# SCH_ERangerBeads_2023-05-25.net
KiCad netlist of a schematic drawn in EasyEDA
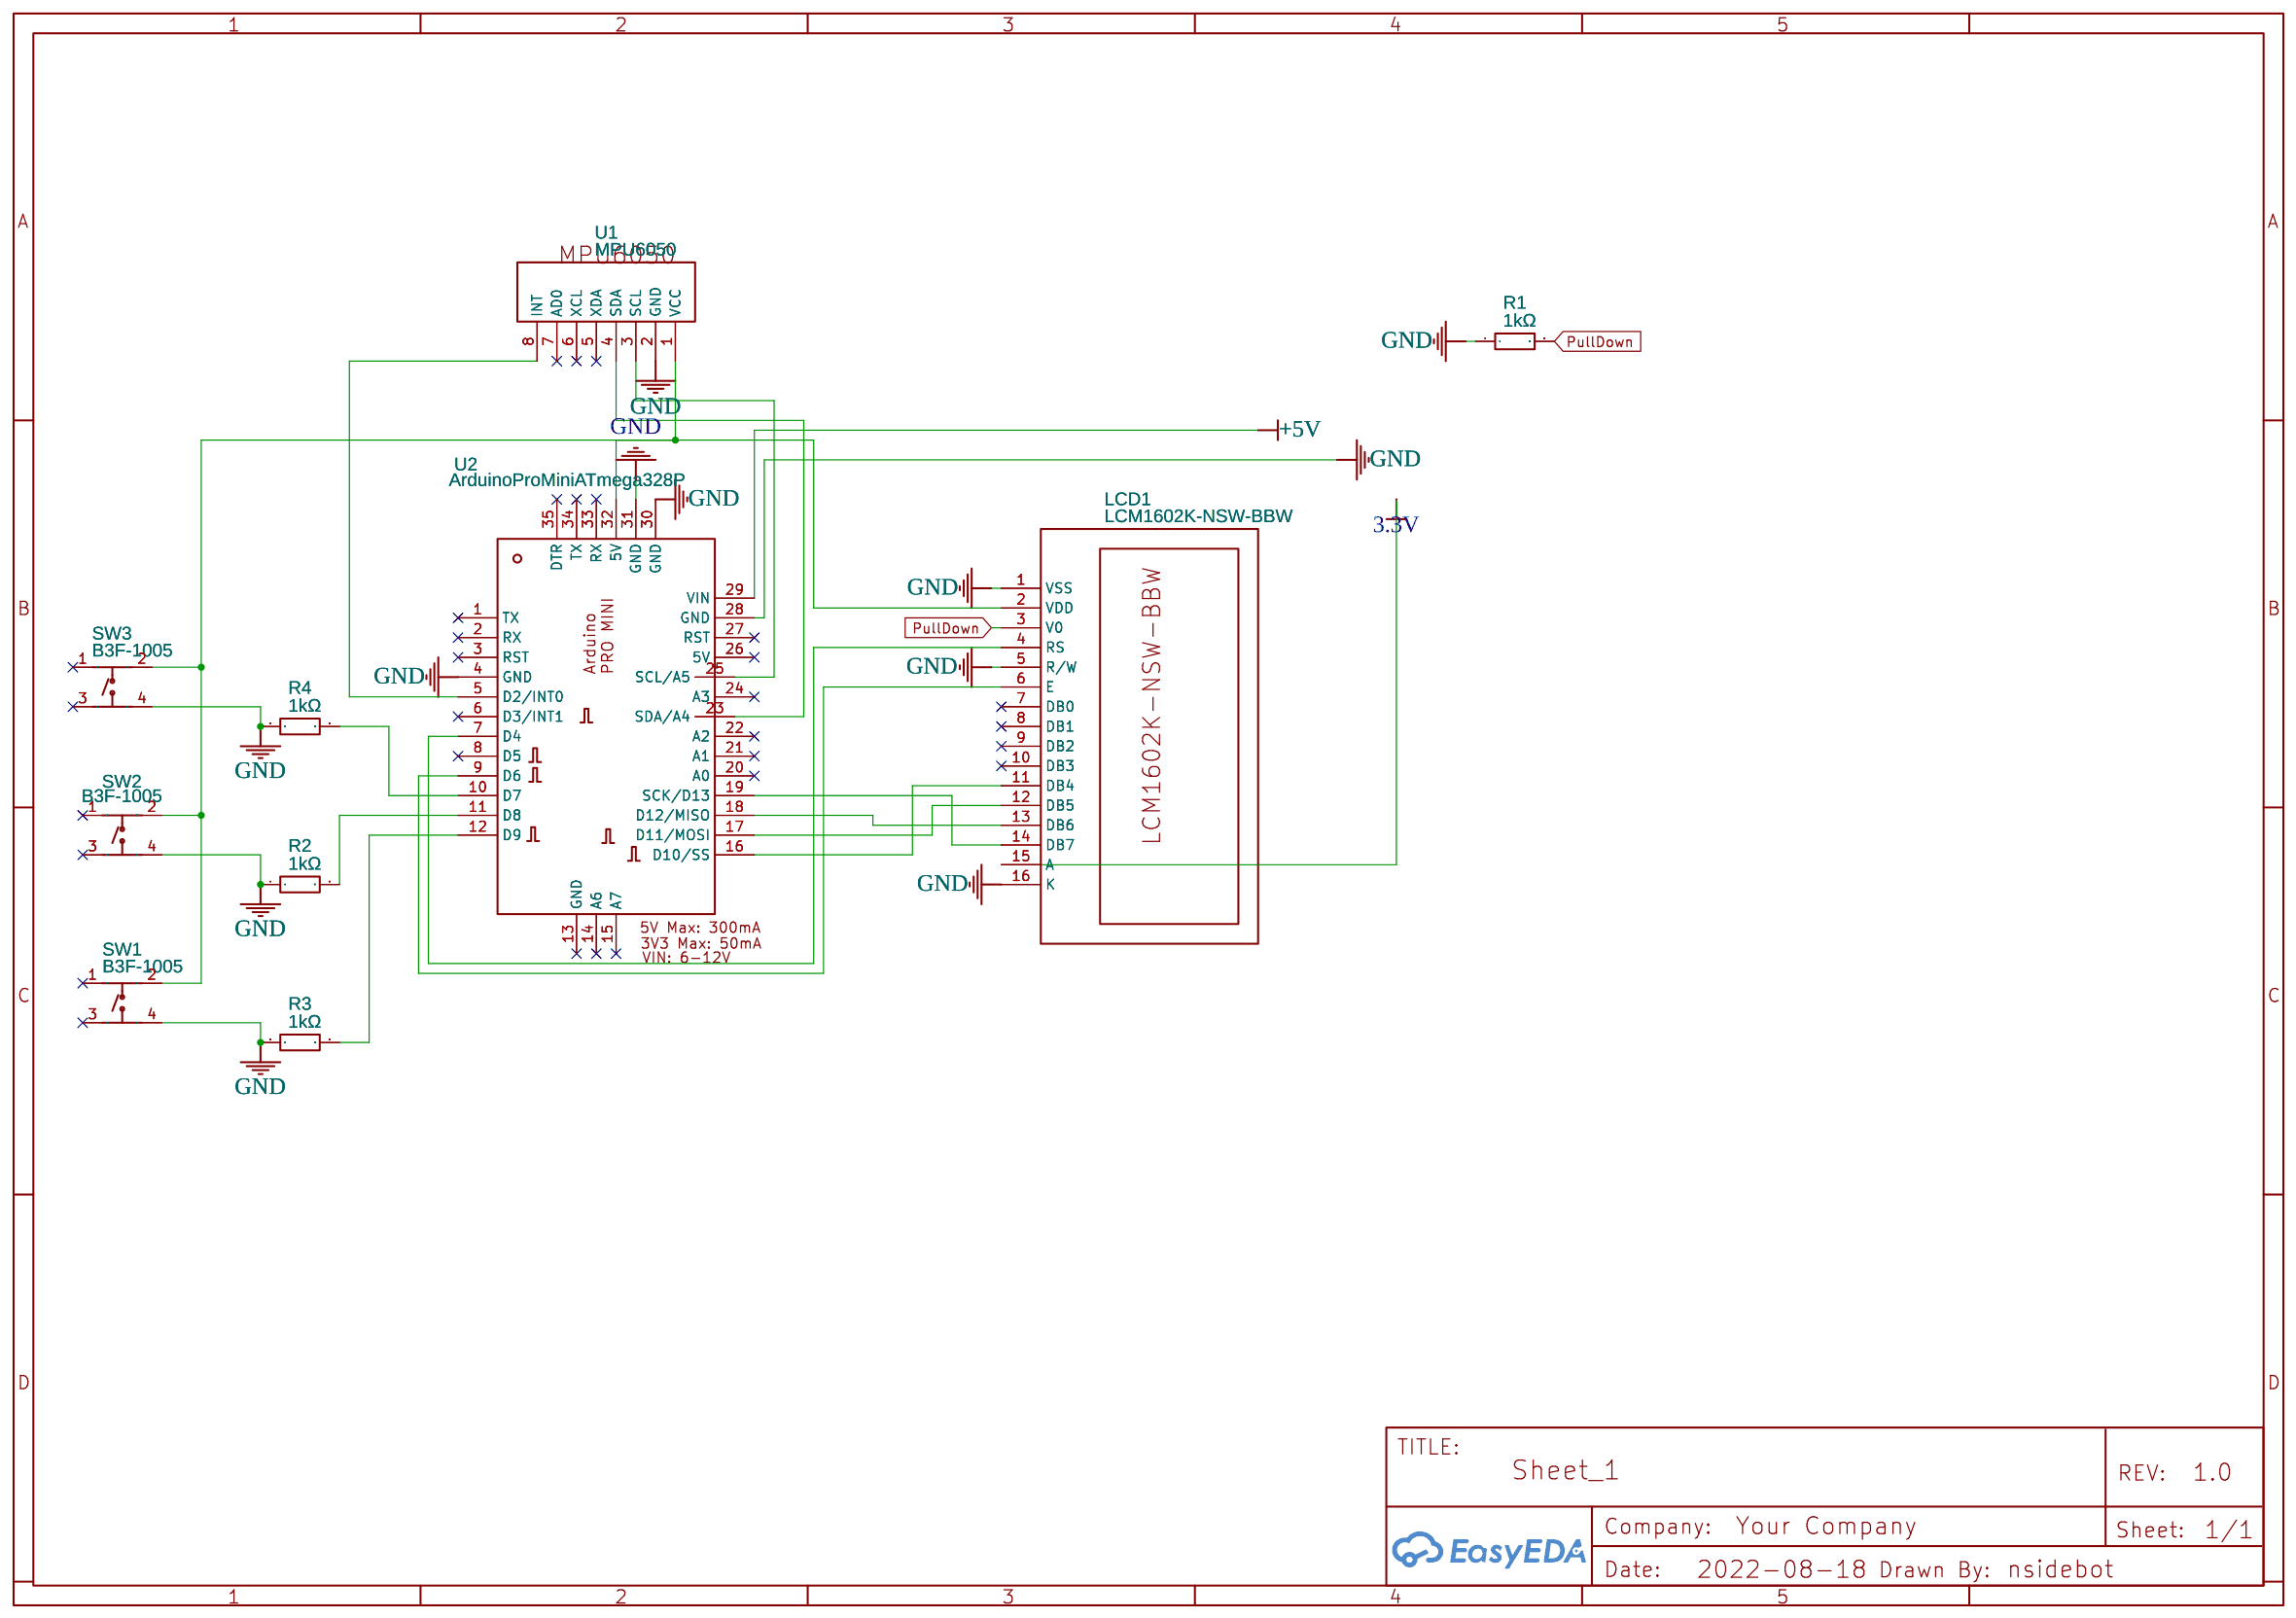
[diagram p0: schematic sheet]

(export (version "E")
  (design (tool "Eeschema 10.0.6"))
  (components
    (comp (ref "LCD1")
      (value "LCM1602K-NSW-BBW")
      (fields (field (name "BOM_Supplier Part") "C83275"))
      (libsource (lib "") (part "LCM1602K-NSW-BBW"))
    )
    (comp (ref "R1")
      (value "1kΩ")
      (fields
        (field (name "BOM_Manufacturer Part") "0603WAJ0102T5E")
        (field (name "BOM_Supplier Part") "C25585")
      )
      (libsource (lib "") (part "0603WAJ0102T5E"))
    )
    (comp (ref "R2")
      (value "1kΩ")
      (fields
        (field (name "BOM_Manufacturer Part") "0603WAJ0102T5E")
        (field (name "BOM_Supplier Part") "C25585")
      )
      (libsource (lib "") (part "0603WAJ0102T5E"))
    )
    (comp (ref "R3")
      (value "1kΩ")
      (fields
        (field (name "BOM_Manufacturer Part") "0603WAJ0102T5E")
        (field (name "BOM_Supplier Part") "C25585")
      )
      (libsource (lib "") (part "0603WAJ0102T5E"))
    )
    (comp (ref "R4")
      (value "1kΩ")
      (fields
        (field (name "BOM_Manufacturer Part") "0603WAJ0102T5E")
        (field (name "BOM_Supplier Part") "C25585")
      )
      (libsource (lib "") (part "0603WAJ0102T5E"))
    )
    (comp (ref "SW1")
      (value "B3F-1005")
      (fields (field (name "BOM_Supplier Part") "C397293"))
      (libsource (lib "") (part "B3F-1005"))
    )
    (comp (ref "SW2")
      (value "B3F-1005")
      (fields (field (name "BOM_Supplier Part") "C397293"))
      (libsource (lib "") (part "B3F-1005"))
    )
    (comp (ref "SW3")
      (value "B3F-1005")
      (fields (field (name "BOM_Supplier Part") "C397293"))
      (libsource (lib "") (part "B3F-1005"))
    )
    (comp (ref "U1") (value "MPU6050") (libsource (lib "") (part "MPU6050")))
    (comp (ref "U2")
      (value "ArduinoProMiniATmega328P")
      (libsource (lib "") (part "ArduinoProMiniATmega328P"))
    )
  )
  (nets
    (net (code "1") (name "+5V") (class "Default")
      (node (ref "U2") (pin "29") (pinfunction "VIN_29") (pintype "unspecified"))
    )
    (net (code "2") (name "3.3V") (class "Default")
      (node (ref "LCD1") (pin "15") (pinfunction "A_15") (pintype "unspecified"))
    )
    (net (code "3") (name "GND") (class "Default")
      (node (ref "LCD1") (pin "1") (pinfunction "VSS_1") (pintype "unspecified"))
      (node (ref "LCD1") (pin "16") (pinfunction "K_16") (pintype "unspecified"))
      (node (ref "LCD1") (pin "5") (pinfunction "R/W_5") (pintype "unspecified"))
      (node (ref "R1") (pin "1") (pinfunction "1_1") (pintype "input"))
      (node (ref "R2") (pin "1") (pinfunction "1_1") (pintype "input"))
      (node (ref "R3") (pin "1") (pinfunction "1_1") (pintype "input"))
      (node (ref "R4") (pin "1") (pinfunction "1_1") (pintype "input"))
      (node (ref "SW1") (pin "4") (pinfunction "4_4") (pintype "unspecified"))
      (node (ref "SW2") (pin "4") (pinfunction "4_4") (pintype "unspecified"))
      (node (ref "SW3") (pin "4") (pinfunction "4_4") (pintype "unspecified"))
      (node (ref "U1") (pin "2") (pinfunction "GND_2") (pintype "unspecified"))
      (node (ref "U2") (pin "28") (pinfunction "GND_28") (pintype "unspecified"))
      (node (ref "U2") (pin "30") (pinfunction "GND_30") (pintype "unspecified"))
      (node (ref "U2") (pin "31") (pinfunction "GND_31") (pintype "unspecified"))
      (node (ref "U2") (pin "4") (pinfunction "GND_4") (pintype "unspecified"))
    )
    (net (code "4") (name "Net-(LCD1-DB4)") (class "Default")
      (node (ref "LCD1") (pin "11") (pinfunction "DB4_11") (pintype "unspecified"))
      (node (ref "U2") (pin "16") (pinfunction "D10/SS_16") (pintype "unspecified"))
    )
    (net (code "5") (name "Net-(LCD1-DB5)") (class "Default")
      (node (ref "LCD1") (pin "12") (pinfunction "DB5_12") (pintype "unspecified"))
      (node (ref "U2") (pin "17") (pinfunction "D11/MOSI_17") (pintype "unspecified"))
    )
    (net (code "6") (name "Net-(LCD1-DB6)") (class "Default")
      (node (ref "LCD1") (pin "13") (pinfunction "DB6_13") (pintype "unspecified"))
      (node (ref "U2") (pin "18") (pinfunction "D12/MISO_18") (pintype "unspecified"))
    )
    (net (code "7") (name "Net-(LCD1-DB7)") (class "Default")
      (node (ref "LCD1") (pin "14") (pinfunction "DB7_14") (pintype "unspecified"))
      (node (ref "U2") (pin "19") (pinfunction "SCK/D13_19") (pintype "unspecified"))
    )
    (net (code "8") (name "Net-(LCD1-E)") (class "Default")
      (node (ref "LCD1") (pin "6") (pinfunction "E_6") (pintype "unspecified"))
      (node (ref "U2") (pin "9") (pinfunction "D6_9") (pintype "unspecified"))
    )
    (net (code "9") (name "Net-(LCD1-RS)") (class "Default")
      (node (ref "LCD1") (pin "4") (pinfunction "RS_4") (pintype "unspecified"))
      (node (ref "U2") (pin "7") (pinfunction "D4_7") (pintype "unspecified"))
    )
    (net (code "10") (name "Net-(LCD1-VDD)") (class "Default")
      (node (ref "LCD1") (pin "2") (pinfunction "VDD_2") (pintype "unspecified"))
      (node (ref "SW1") (pin "2") (pinfunction "2_2") (pintype "unspecified"))
      (node (ref "SW2") (pin "2") (pinfunction "2_2") (pintype "unspecified"))
      (node (ref "SW3") (pin "2") (pinfunction "2_2") (pintype "unspecified"))
      (node (ref "U1") (pin "1") (pinfunction "VCC_1") (pintype "unspecified"))
      (node (ref "U2") (pin "32") (pinfunction "5V_32") (pintype "unspecified"))
    )
    (net (code "11") (name "Net-(U1-INT)") (class "Default")
      (node (ref "U1") (pin "8") (pinfunction "INT_8") (pintype "unspecified"))
      (node (ref "U2") (pin "5") (pinfunction "D2/INT0_5") (pintype "unspecified"))
    )
    (net (code "12") (name "Net-(U1-SCL)") (class "Default")
      (node (ref "U1") (pin "3") (pinfunction "SCL_3") (pintype "unspecified"))
      (node (ref "U2") (pin "25") (pinfunction "SCL/A5_25") (pintype "unspecified"))
    )
    (net (code "13") (name "Net-(U1-SDA)") (class "Default")
      (node (ref "U1") (pin "4") (pinfunction "SDA_4") (pintype "unspecified"))
      (node (ref "U2") (pin "23") (pinfunction "SDA/A4_23") (pintype "unspecified"))
    )
    (net (code "14") (name "Net-(U2-D7)") (class "Default")
      (node (ref "R4") (pin "2") (pinfunction "2_2") (pintype "input"))
      (node (ref "U2") (pin "10") (pinfunction "D7_10") (pintype "unspecified"))
    )
    (net (code "15") (name "Net-(U2-D8)") (class "Default")
      (node (ref "R2") (pin "2") (pinfunction "2_2") (pintype "input"))
      (node (ref "U2") (pin "11") (pinfunction "D8_11") (pintype "unspecified"))
    )
    (net (code "16") (name "Net-(U2-D9)") (class "Default")
      (node (ref "R3") (pin "2") (pinfunction "2_2") (pintype "input"))
      (node (ref "U2") (pin "12") (pinfunction "D9_12") (pintype "unspecified"))
    )
    (net (code "17") (name "PullDown") (class "Default")
      (node (ref "LCD1") (pin "3") (pinfunction "V0_3") (pintype "unspecified"))
      (node (ref "R1") (pin "2") (pinfunction "2_2") (pintype "input"))
    )
    (net (code "18") (name "unconnected-(LCD1-DB0-Pad7)") (class "Default")
      (node (ref "LCD1") (pin "7") (pinfunction "DB0_7") (pintype "unspecified+no_connect"))
    )
    (net (code "19") (name "unconnected-(LCD1-DB1-Pad8)") (class "Default")
      (node (ref "LCD1") (pin "8") (pinfunction "DB1_8") (pintype "unspecified+no_connect"))
    )
    (net (code "20") (name "unconnected-(LCD1-DB2-Pad9)") (class "Default")
      (node (ref "LCD1") (pin "9") (pinfunction "DB2_9") (pintype "unspecified+no_connect"))
    )
    (net (code "21") (name "unconnected-(LCD1-DB3-Pad10)") (class "Default")
      (node (ref "LCD1") (pin "10") (pinfunction "DB3_10") (pintype "unspecified+no_connect"))
    )
    (net (code "22") (name "unconnected-(SW1-Pad1)") (class "Default")
      (node (ref "SW1") (pin "1") (pinfunction "1_1") (pintype "unspecified+no_connect"))
    )
    (net (code "23") (name "unconnected-(SW1-Pad3)") (class "Default")
      (node (ref "SW1") (pin "3") (pinfunction "3_3") (pintype "unspecified+no_connect"))
    )
    (net (code "24") (name "unconnected-(SW2-Pad1)") (class "Default")
      (node (ref "SW2") (pin "1") (pinfunction "1_1") (pintype "unspecified+no_connect"))
    )
    (net (code "25") (name "unconnected-(SW2-Pad3)") (class "Default")
      (node (ref "SW2") (pin "3") (pinfunction "3_3") (pintype "unspecified+no_connect"))
    )
    (net (code "26") (name "unconnected-(SW3-Pad1)") (class "Default")
      (node (ref "SW3") (pin "1") (pinfunction "1_1") (pintype "unspecified+no_connect"))
    )
    (net (code "27") (name "unconnected-(SW3-Pad3)") (class "Default")
      (node (ref "SW3") (pin "3") (pinfunction "3_3") (pintype "unspecified+no_connect"))
    )
    (net (code "28") (name "unconnected-(U1-AD0-Pad7)") (class "Default")
      (node (ref "U1") (pin "7") (pinfunction "AD0_7") (pintype "unspecified+no_connect"))
    )
    (net (code "29") (name "unconnected-(U1-XCL-Pad6)") (class "Default")
      (node (ref "U1") (pin "6") (pinfunction "XCL_6") (pintype "unspecified+no_connect"))
    )
    (net (code "30") (name "unconnected-(U1-XDA-Pad5)") (class "Default")
      (node (ref "U1") (pin "5") (pinfunction "XDA_5") (pintype "unspecified+no_connect"))
    )
    (net (code "31") (name "unconnected-(U2-5V-Pad26)") (class "Default")
      (node (ref "U2") (pin "26") (pinfunction "5V_26") (pintype "unspecified+no_connect"))
    )
    (net (code "32") (name "unconnected-(U2-A0-Pad20)") (class "Default")
      (node (ref "U2") (pin "20") (pinfunction "A0_20") (pintype "unspecified+no_connect"))
    )
    (net (code "33") (name "unconnected-(U2-A1-Pad21)") (class "Default")
      (node (ref "U2") (pin "21") (pinfunction "A1_21") (pintype "unspecified+no_connect"))
    )
    (net (code "34") (name "unconnected-(U2-A2-Pad22)") (class "Default")
      (node (ref "U2") (pin "22") (pinfunction "A2_22") (pintype "unspecified+no_connect"))
    )
    (net (code "35") (name "unconnected-(U2-A3-Pad24)") (class "Default")
      (node (ref "U2") (pin "24") (pinfunction "A3_24") (pintype "unspecified+no_connect"))
    )
    (net (code "36") (name "unconnected-(U2-A6-Pad14)") (class "Default")
      (node (ref "U2") (pin "14") (pinfunction "A6_14") (pintype "unspecified+no_connect"))
    )
    (net (code "37") (name "unconnected-(U2-A7-Pad15)") (class "Default")
      (node (ref "U2") (pin "15") (pinfunction "A7_15") (pintype "unspecified+no_connect"))
    )
    (net (code "38") (name "unconnected-(U2-D3{slash}INT1-Pad6)") (class "Default")
      (node (ref "U2") (pin "6") (pinfunction "D3/INT1_6") (pintype "unspecified+no_connect"))
    )
    (net (code "39") (name "unconnected-(U2-D5-Pad8)") (class "Default")
      (node (ref "U2") (pin "8") (pinfunction "D5_8") (pintype "unspecified+no_connect"))
    )
    (net (code "40") (name "unconnected-(U2-DTR-Pad35)") (class "Default")
      (node (ref "U2") (pin "35") (pinfunction "DTR_35") (pintype "unspecified+no_connect"))
    )
    (net (code "41") (name "unconnected-(U2-GND-Pad13)") (class "Default")
      (node (ref "U2") (pin "13") (pinfunction "GND_13") (pintype "unspecified+no_connect"))
    )
    (net (code "42") (name "unconnected-(U2-RST-Pad3)") (class "Default")
      (node (ref "U2") (pin "3") (pinfunction "RST_3") (pintype "unspecified+no_connect"))
    )
    (net (code "43") (name "unconnected-(U2-RST-Pad27)") (class "Default")
      (node (ref "U2") (pin "27") (pinfunction "RST_27") (pintype "unspecified+no_connect"))
    )
    (net (code "44") (name "unconnected-(U2-RX-Pad2)") (class "Default")
      (node (ref "U2") (pin "2") (pinfunction "RX_2") (pintype "unspecified+no_connect"))
    )
    (net (code "45") (name "unconnected-(U2-RX-Pad33)") (class "Default")
      (node (ref "U2") (pin "33") (pinfunction "RX_33") (pintype "unspecified+no_connect"))
    )
    (net (code "46") (name "unconnected-(U2-TX-Pad1)") (class "Default")
      (node (ref "U2") (pin "1") (pinfunction "TX_1") (pintype "unspecified+no_connect"))
    )
    (net (code "47") (name "unconnected-(U2-TX-Pad34)") (class "Default")
      (node (ref "U2") (pin "34") (pinfunction "TX_34") (pintype "unspecified+no_connect"))
    )
  )
)
